# opamp_cc_load.net
KiCad netlist of a schematic drawn in EAGLE
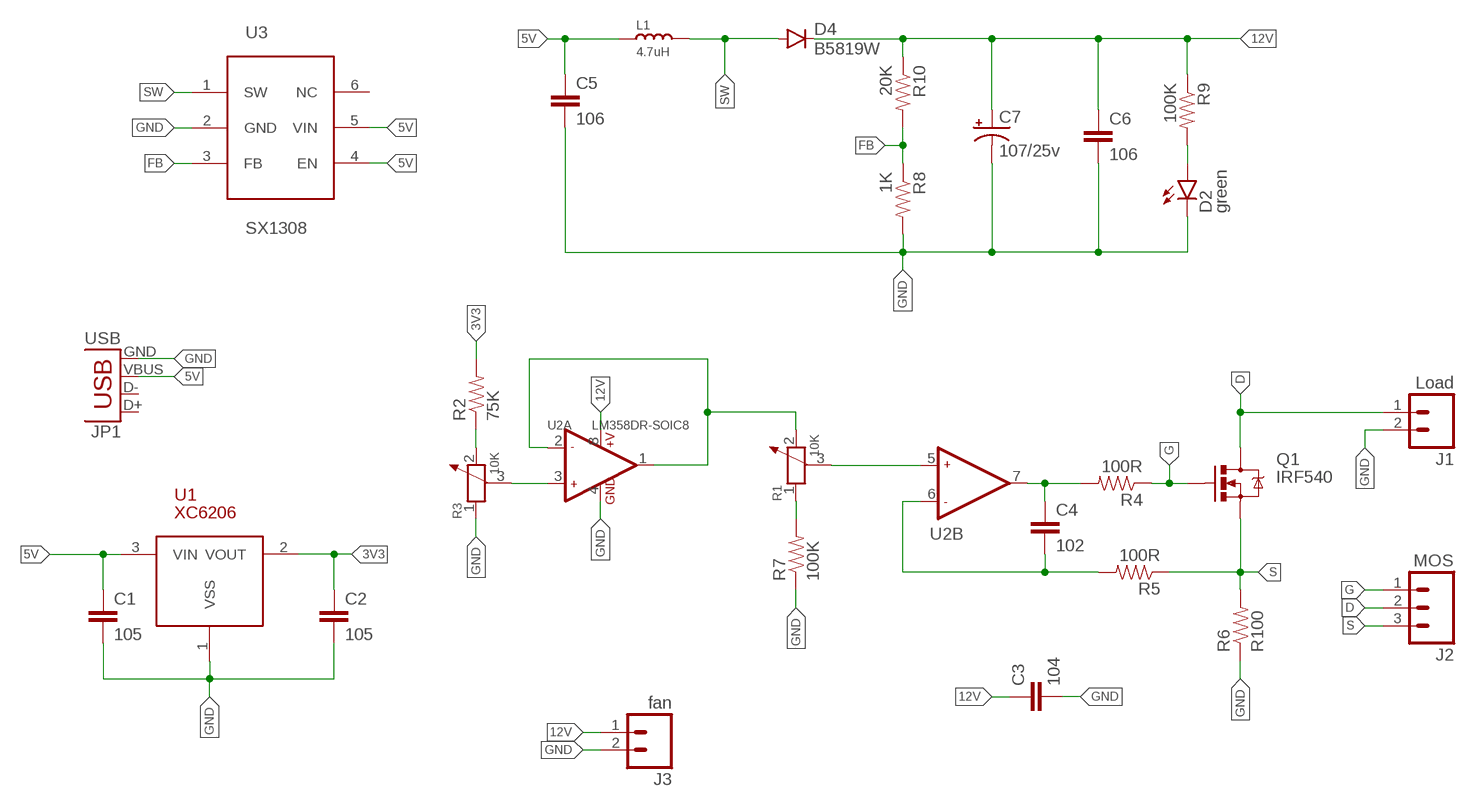
[diagram p0: schematic, sheet 1]

(export (version "E")
  (design (tool "Eeschema 10.0.6"))
  (components
    (comp (ref "C1")
      (value "105")
      (footprint "eagle-import:0603-CAP")
      (libsource (lib "eagle-import") (part "CAP0603-CAP"))
    )
    (comp (ref "C2")
      (value "105")
      (footprint "eagle-import:0603-CAP")
      (libsource (lib "eagle-import") (part "CAP0603-CAP"))
    )
    (comp (ref "C3")
      (value "104")
      (footprint "eagle-import:0603-CAP")
      (libsource (lib "eagle-import") (part "CAP0603-CAP"))
    )
    (comp (ref "C4")
      (value "102")
      (footprint "eagle-import:0603-CAP")
      (libsource (lib "eagle-import") (part "CAP0603-CAP"))
    )
    (comp (ref "C5")
      (value "106")
      (footprint "eagle-import:1206")
      (libsource (lib "eagle-import") (part "CAP1206"))
    )
    (comp (ref "C6")
      (value "106")
      (footprint "eagle-import:1206")
      (libsource (lib "eagle-import") (part "CAP1206"))
    )
    (comp (ref "C7")
      (value "107/25v")
      (footprint "eagle-import:CPOL-RADIAL-100UF-25V")
      (libsource (lib "eagle-import") (part "CAP_POLPTH1"))
    )
    (comp (ref "D2")
      (value "green")
      (footprint "eagle-import:LED-0603-SEEED")
      (libsource (lib "eagle-import") (part "LED-SEEED-0603"))
    )
    (comp (ref "D4")
      (value "B5819W")
      (footprint "eagle-import:SOD-123")
      (libsource (lib "eagle-import") (part "DIODESOD123"))
    )
    (comp (ref "J1")
      (value "Load")
      (footprint "eagle-import:SCREWTERMINAL-5MM-2")
      (libsource (lib "eagle-import") (part "M025MM"))
    )
    (comp (ref "J2")
      (value "MOS")
      (footprint "eagle-import:SCREWTERMINAL-5MM-3")
      (libsource (lib "eagle-import") (part "M03-SCREW-5MM"))
    )
    (comp (ref "J3")
      (value "fan")
      (footprint "eagle-import:1X02_NO_SILK")
      (libsource (lib "eagle-import") (part "M021X02_NO_SILK"))
    )
    (comp (ref "JP1")
      (value "USB")
      (footprint "eagle-import:MICROUSB-U-F-M5DD-Y-1")
      (libsource (lib "eagle-import") (part "USB"))
    )
    (comp (ref "L1")
      (value "4.7uH")
      (footprint "eagle-import:SMD-2P-5.0X5.0X2.0MM")
      (fields (field (name "MPN") "SWPA5020S220MT"))
      (libsource (lib "eagle-import") (part "SMD-INDUCTOR-200UH-20%(2P-5X5MM)"))
    )
    (comp (ref "Q1")
      (value "IRF540")
      (footprint "eagle-import:TO220V")
      (libsource (lib "eagle-import") (part "MOSFET-NCHANNELFQP30N06L"))
    )
    (comp (ref "R1")
      (value "10K")
      (footprint "eagle-import:ADJR3-7.0X7.0X5.0MM")
      (fields (field (name "MPN") "SX3362P"))
      (libsource (lib "eagle-import") (part "DIP-VR-TOP-ADJ-10K-3362P(3P-7.0X7.0X5.0MM)"))
    )
    (comp (ref "R2")
      (value "75K")
      (footprint "eagle-import:0603-RES")
      (libsource (lib "eagle-import") (part "RESISTOR0603"))
    )
    (comp (ref "R3")
      (value "10K")
      (footprint "eagle-import:ADJR3-7.0X7.0X5.0MM")
      (fields (field (name "MPN") "SX3362P"))
      (libsource (lib "eagle-import") (part "DIP-VR-TOP-ADJ-10K-3362P(3P-7.0X7.0X5.0MM)"))
    )
    (comp (ref "R4")
      (value "100R")
      (footprint "eagle-import:0603-RES")
      (libsource (lib "eagle-import") (part "RESISTOR0603"))
    )
    (comp (ref "R5")
      (value "100R")
      (footprint "eagle-import:0603-RES")
      (libsource (lib "eagle-import") (part "RESISTOR0603"))
    )
    (comp (ref "R6")
      (value "R100")
      (footprint "eagle-import:R2512")
      (libsource (lib "eagle-import") (part "RESISTOR2512"))
    )
    (comp (ref "R7")
      (value "100K")
      (footprint "eagle-import:0603-RES")
      (libsource (lib "eagle-import") (part "RESISTOR0603"))
    )
    (comp (ref "R8")
      (value "1K")
      (footprint "eagle-import:0603-RES")
      (libsource (lib "eagle-import") (part "RESISTOR0603"))
    )
    (comp (ref "R9")
      (value "100K")
      (footprint "eagle-import:0603-RES")
      (libsource (lib "eagle-import") (part "RESISTOR0603"))
    )
    (comp (ref "R10")
      (value "20K")
      (footprint "eagle-import:0603-RES")
      (libsource (lib "eagle-import") (part "RESISTOR0603"))
    )
    (comp (ref "U1")
      (value "XC6206")
      (footprint "eagle-import:SOT23-3")
      (libsource (lib "eagle-import") (part "XC6206"))
    )
    (comp (ref "U2")
      (value "LM358DR-SOIC8")
      (footprint "eagle-import:SOIC8-1.27-5X4MM")
      (fields (field (name "MPN") "LM358DR"))
      (libsource (lib "eagle-import") (part "AMPLIFIER-LM358DR(SOIC8)"))
    )
    (comp (ref "U3")
      (value "SX1308")
      (footprint "eagle-import:SOT23-6")
      (libsource (lib "eagle-import") (part "SX1308"))
    )
  )
  (nets
    (net (code "1") (name "3V3") (class "Default")
      (node (ref "C2") (pin "1") (pinfunction "1_1") (pintype "passive"))
      (node (ref "R2") (pin "2") (pinfunction "2_2") (pintype "passive"))
      (node (ref "U1") (pin "2") (pinfunction "VOUT_2") (pintype "power_in"))
    )
    (net (code "2") (name "5V") (class "Default")
      (node (ref "C1") (pin "1") (pinfunction "1_1") (pintype "passive"))
      (node (ref "C5") (pin "1") (pinfunction "1_1") (pintype "passive"))
      (node (ref "JP1") (pin "VBUS") (pinfunction "VBUS_VBUS") (pintype "bidirectional"))
      (node (ref "L1") (pin "1") (pinfunction "1_1") (pintype "passive"))
      (node (ref "U1") (pin "3") (pinfunction "VIN_3") (pintype "power_in"))
      (node (ref "U3") (pin "4") (pinfunction "EN_4") (pintype "bidirectional"))
      (node (ref "U3") (pin "5") (pinfunction "VIN_5") (pintype "bidirectional"))
    )
    (net (code "3") (name "12V") (class "Default")
      (node (ref "C3") (pin "1") (pinfunction "1_1") (pintype "passive"))
      (node (ref "C6") (pin "1") (pinfunction "1_1") (pintype "passive"))
      (node (ref "C7") (pin "1") (pinfunction "+_1") (pintype "passive"))
      (node (ref "D4") (pin "C") (pinfunction "C_C") (pintype "passive"))
      (node (ref "J3") (pin "1") (pinfunction "1_1") (pintype "passive"))
      (node (ref "R10") (pin "1") (pinfunction "1_1") (pintype "passive"))
      (node (ref "R9") (pin "1") (pinfunction "1_1") (pintype "passive"))
      (node (ref "U2") (pin "8") (pinfunction "+V_8") (pintype "power_in"))
    )
    (net (code "4") (name "D") (class "Default")
      (node (ref "J1") (pin "1") (pinfunction "1_1") (pintype "passive"))
      (node (ref "J2") (pin "2") (pinfunction "2_2") (pintype "passive"))
      (node (ref "Q1") (pin "2") (pinfunction "D_2") (pintype "passive"))
    )
    (net (code "5") (name "FB") (class "Default")
      (node (ref "R10") (pin "2") (pinfunction "2_2") (pintype "passive"))
      (node (ref "R8") (pin "1") (pinfunction "1_1") (pintype "passive"))
      (node (ref "U3") (pin "3") (pinfunction "FB_3") (pintype "bidirectional"))
    )
    (net (code "6") (name "G") (class "Default")
      (node (ref "J2") (pin "1") (pinfunction "1_1") (pintype "passive"))
      (node (ref "Q1") (pin "1") (pinfunction "G_1") (pintype "passive"))
      (node (ref "R4") (pin "1") (pinfunction "1_1") (pintype "passive"))
    )
    (net (code "7") (name "GND") (class "Default")
      (node (ref "C1") (pin "2") (pinfunction "2_2") (pintype "passive"))
      (node (ref "C2") (pin "2") (pinfunction "2_2") (pintype "passive"))
      (node (ref "C3") (pin "2") (pinfunction "2_2") (pintype "passive"))
      (node (ref "C5") (pin "2") (pinfunction "2_2") (pintype "passive"))
      (node (ref "C6") (pin "2") (pinfunction "2_2") (pintype "passive"))
      (node (ref "C7") (pin "2") (pinfunction "-_2") (pintype "passive"))
      (node (ref "D2") (pin "-") (pinfunction "C_-") (pintype "passive"))
      (node (ref "J1") (pin "2") (pinfunction "2_2") (pintype "passive"))
      (node (ref "J3") (pin "2") (pinfunction "2_2") (pintype "passive"))
      (node (ref "JP1") (pin "GND") (pinfunction "GND_GND") (pintype "bidirectional"))
      (node (ref "R3") (pin "1") (pinfunction "1_1") (pintype "passive"))
      (node (ref "R6") (pin "1") (pinfunction "1_1") (pintype "passive"))
      (node (ref "R7") (pin "1") (pinfunction "1_1") (pintype "passive"))
      (node (ref "R8") (pin "2") (pinfunction "2_2") (pintype "passive"))
      (node (ref "U1") (pin "1") (pinfunction "VSS_1") (pintype "passive"))
      (node (ref "U2") (pin "4") (pinfunction "GND_4") (pintype "power_in"))
      (node (ref "U3") (pin "2") (pinfunction "GND_2") (pintype "bidirectional"))
    )
    (net (code "8") (name "Net-(D2-A)") (class "Default")
      (node (ref "D2") (pin "+") (pinfunction "A_+") (pintype "passive"))
      (node (ref "R9") (pin "2") (pinfunction "2_2") (pintype "passive"))
    )
    (net (code "9") (name "Net-(R1-2)") (class "Default")
      (node (ref "R1") (pin "3") (pinfunction "2_3") (pintype "passive"))
      (node (ref "U2") (pin "5") (pinfunction "+IN2_5") (pintype "input"))
    )
    (net (code "10") (name "Net-(R1-3)") (class "Default")
      (node (ref "R1") (pin "2") (pinfunction "3_2") (pintype "passive"))
      (node (ref "U2") (pin "1") (pinfunction "OUT1_1") (pintype "output"))
      (node (ref "U2") (pin "2") (pinfunction "-IN1_2") (pintype "input"))
    )
    (net (code "11") (name "Net-(R1-Pad1)") (class "Default")
      (node (ref "R1") (pin "1") (pinfunction "1_1") (pintype "passive"))
      (node (ref "R7") (pin "2") (pinfunction "2_2") (pintype "passive"))
    )
    (net (code "12") (name "Net-(R3-2)") (class "Default")
      (node (ref "R3") (pin "3") (pinfunction "2_3") (pintype "passive"))
      (node (ref "U2") (pin "3") (pinfunction "+IN1_3") (pintype "input"))
    )
    (net (code "13") (name "Net-(R3-3)") (class "Default")
      (node (ref "R2") (pin "1") (pinfunction "1_1") (pintype "passive"))
      (node (ref "R3") (pin "2") (pinfunction "3_2") (pintype "passive"))
    )
    (net (code "14") (name "Net-(U2B--IN2)") (class "Default")
      (node (ref "C4") (pin "2") (pinfunction "2_2") (pintype "passive"))
      (node (ref "R5") (pin "2") (pinfunction "2_2") (pintype "passive"))
      (node (ref "U2") (pin "6") (pinfunction "-IN2_6") (pintype "input"))
    )
    (net (code "15") (name "Net-(U2B-OUT2)") (class "Default")
      (node (ref "C4") (pin "1") (pinfunction "1_1") (pintype "passive"))
      (node (ref "R4") (pin "2") (pinfunction "2_2") (pintype "passive"))
      (node (ref "U2") (pin "7") (pinfunction "OUT2_7") (pintype "output"))
    )
    (net (code "16") (name "S") (class "Default")
      (node (ref "J2") (pin "3") (pinfunction "3_3") (pintype "passive"))
      (node (ref "Q1") (pin "3") (pinfunction "S_3") (pintype "passive"))
      (node (ref "R5") (pin "1") (pinfunction "1_1") (pintype "passive"))
      (node (ref "R6") (pin "2") (pinfunction "2_2") (pintype "passive"))
    )
    (net (code "17") (name "SW") (class "Default")
      (node (ref "D4") (pin "A") (pinfunction "A_A") (pintype "passive"))
      (node (ref "L1") (pin "2") (pinfunction "2_2") (pintype "passive"))
      (node (ref "U3") (pin "1") (pinfunction "SW_1") (pintype "bidirectional"))
    )
    (net (code "18") (name "unconnected-(JP1-PadD+)") (class "Default")
      (node (ref "JP1") (pin "D+") (pinfunction "D+_D+") (pintype "bidirectional"))
    )
    (net (code "19") (name "unconnected-(JP1-PadD-)") (class "Default")
      (node (ref "JP1") (pin "D-") (pinfunction "D-_D-") (pintype "bidirectional"))
    )
    (net (code "20") (name "unconnected-(U3-NC-Pad6)") (class "Default")
      (node (ref "U3") (pin "6") (pinfunction "NC_6") (pintype "bidirectional"))
    )
  )
)
